# prototype-mark-II.net
KiCad netlist of a schematic drawn in EAGLE
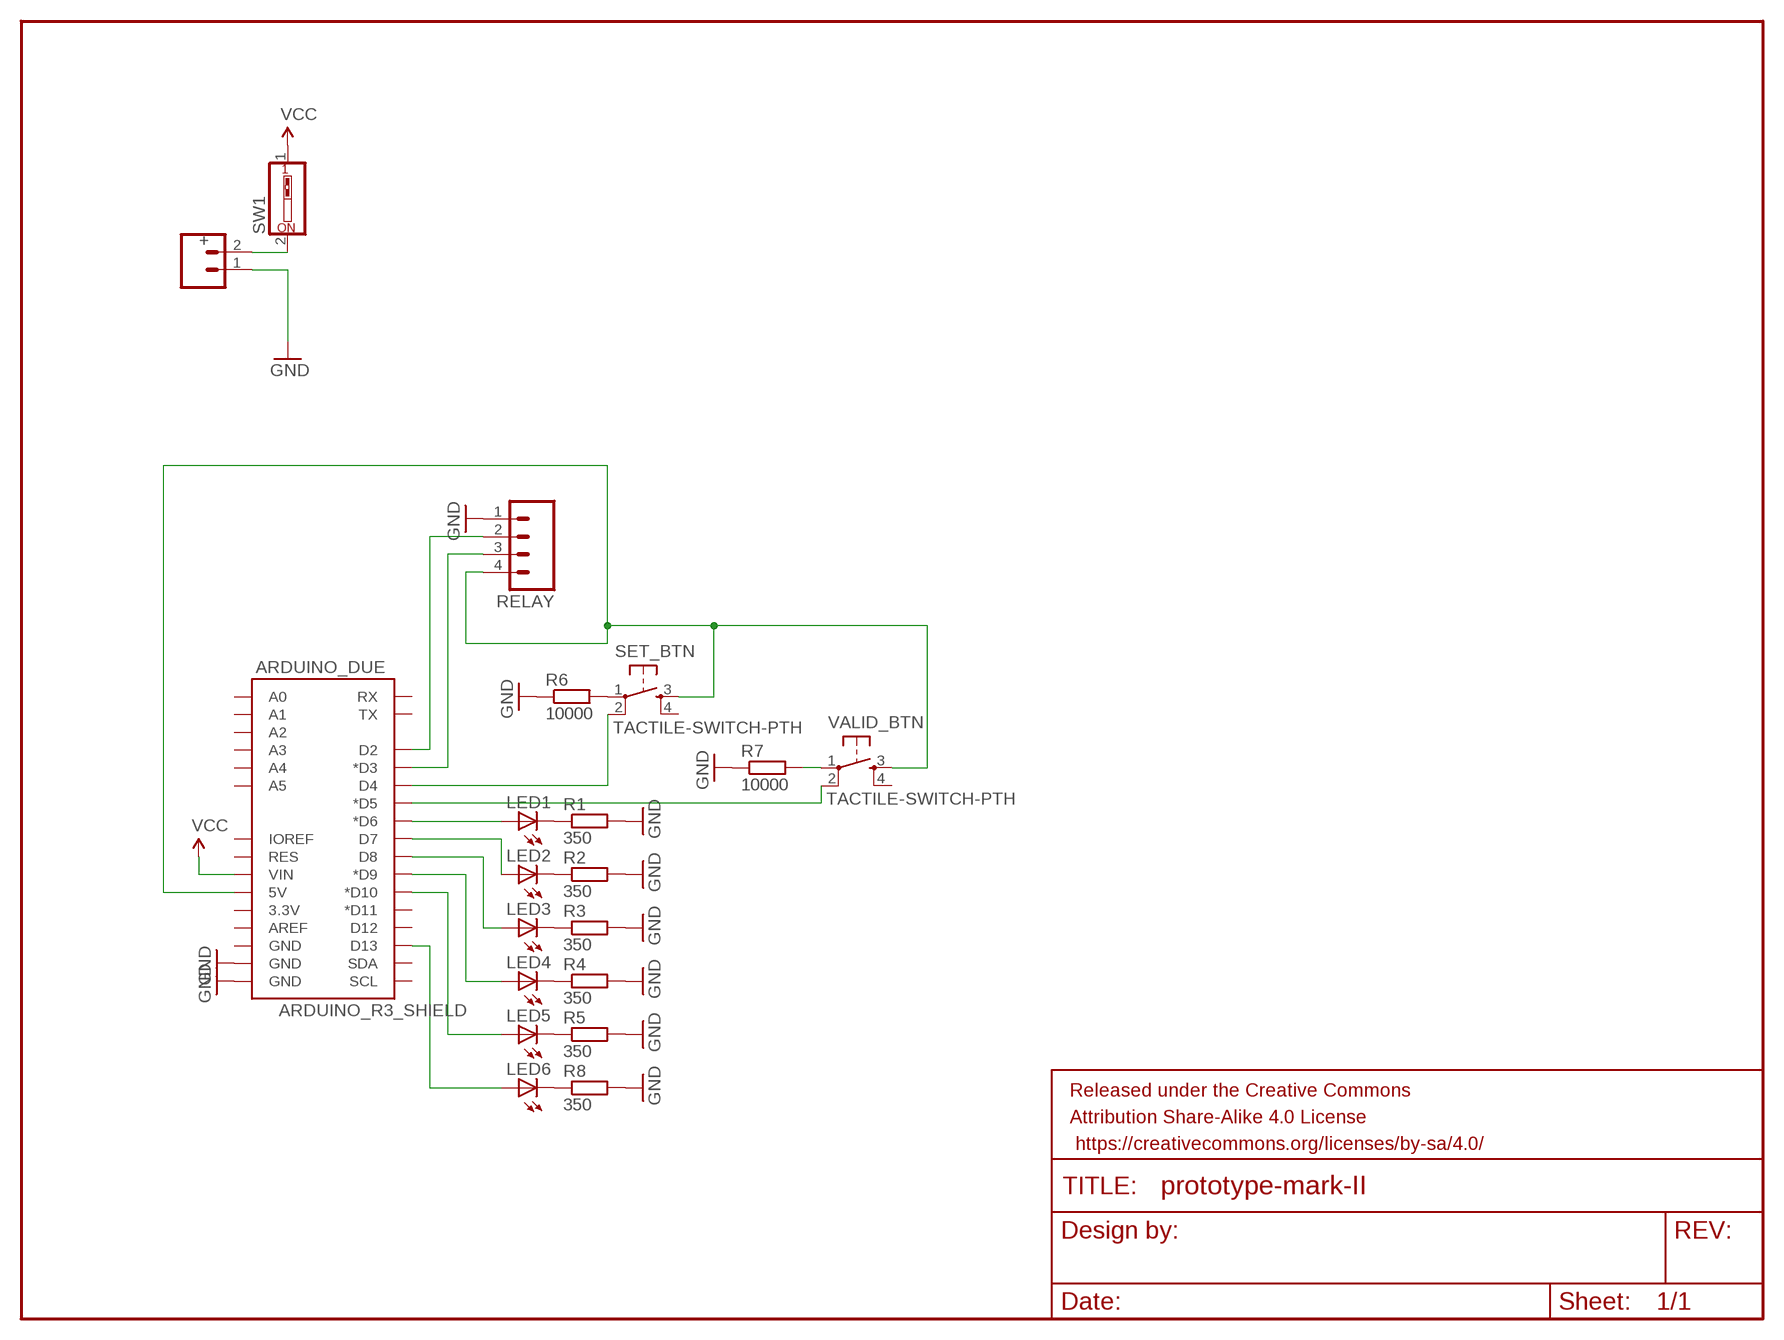
[diagram p0: schematic, sheet 1]

(export (version "E")
  (design (tool "Eeschema 10.0.6"))
  (components
    (comp (ref "+")
      (value "M02PTH")
      (footprint "eagle-import:1X02")
      (libsource (lib "eagle-import") (part "M02PTH"))
    )
    (comp (ref "ARDUINO_DUE")
      (value "ARDUINO_R3_SHIELD")
      (footprint "eagle-import:UNO_R3_SHIELD")
      (libsource (lib "eagle-import") (part "ARDUINO_R3_SHIELD"))
    )
    (comp (ref "FRAME1")
      (value "FRAME-LETTERNO_PACKAGE")
      (footprint "eagle-import:DUMMY")
      (fields (field (name "DESIGNER") "Nobody"))
      (libsource (lib "eagle-import") (part "FRAME-LETTERNO_PACKAGE"))
    )
    (comp (ref "LED1")
      (value "LED3MM")
      (footprint "eagle-import:LED3MM")
      (libsource (lib "eagle-import") (part "LED3MM"))
    )
    (comp (ref "LED2")
      (value "LED3MM")
      (footprint "eagle-import:LED3MM")
      (libsource (lib "eagle-import") (part "LED3MM"))
    )
    (comp (ref "LED3")
      (value "LED3MM")
      (footprint "eagle-import:LED3MM")
      (libsource (lib "eagle-import") (part "LED3MM"))
    )
    (comp (ref "LED4")
      (value "LED3MM")
      (footprint "eagle-import:LED3MM")
      (libsource (lib "eagle-import") (part "LED3MM"))
    )
    (comp (ref "LED5")
      (value "LED3MM")
      (footprint "eagle-import:LED3MM")
      (libsource (lib "eagle-import") (part "LED3MM"))
    )
    (comp (ref "LED6")
      (value "LED3MM")
      (footprint "eagle-import:LED3MM")
      (libsource (lib "eagle-import") (part "LED3MM"))
    )
    (comp (ref "R1")
      (value "350")
      (footprint "eagle-import:0204_7")
      (libsource (lib "eagle-import") (part "R0204/7"))
    )
    (comp (ref "R2")
      (value "350")
      (footprint "eagle-import:0204_7")
      (libsource (lib "eagle-import") (part "R0204/7"))
    )
    (comp (ref "R3")
      (value "350")
      (footprint "eagle-import:0204_7")
      (libsource (lib "eagle-import") (part "R0204/7"))
    )
    (comp (ref "R4")
      (value "350")
      (footprint "eagle-import:0204_7")
      (libsource (lib "eagle-import") (part "R0204/7"))
    )
    (comp (ref "R5")
      (value "350")
      (footprint "eagle-import:0204_7")
      (libsource (lib "eagle-import") (part "R0204/7"))
    )
    (comp (ref "R6")
      (value "10000")
      (footprint "eagle-import:0204_7")
      (libsource (lib "eagle-import") (part "R0204/7"))
    )
    (comp (ref "R7")
      (value "10000")
      (footprint "eagle-import:0204_7")
      (libsource (lib "eagle-import") (part "R0204/7"))
    )
    (comp (ref "R8")
      (value "350")
      (footprint "eagle-import:0204_7")
      (libsource (lib "eagle-import") (part "R0204/7"))
    )
    (comp (ref "RELAY")
      (value "M04PTH")
      (footprint "eagle-import:1X04")
      (libsource (lib "eagle-import") (part "M04PTH"))
    )
    (comp (ref "SET_BTN")
      (value "TACTILE-SWITCH-PTH")
      (footprint "eagle-import:TAC-SWITCH-PTH")
      (libsource (lib "eagle-import") (part "TACTILE-SWITCH-PTH"))
    )
    (comp (ref "SW1")
      (value "SW_DIP-1")
      (footprint "eagle-import:EDG-01")
      (libsource (lib "eagle-import") (part "SW_DIP-1"))
    )
    (comp (ref "VALID_BTN")
      (value "TACTILE-SWITCH-PTH")
      (footprint "eagle-import:TAC-SWITCH-PTH")
      (libsource (lib "eagle-import") (part "TACTILE-SWITCH-PTH"))
    )
  )
  (nets
    (net (code "1") (name "GND") (class "Default")
      (node (ref "+") (pin "1") (pinfunction "1_1") (pintype "passive"))
      (node (ref "ARDUINO_DUE") (pin "GND@0") (pinfunction "GND_GND@0") (pintype "bidirectional"))
      (node (ref "ARDUINO_DUE") (pin "GND@1") (pinfunction "GND_GND@1") (pintype "bidirectional"))
      (node (ref "R1") (pin "2") (pinfunction "2_2") (pintype "passive"))
      (node (ref "R2") (pin "2") (pinfunction "2_2") (pintype "passive"))
      (node (ref "R3") (pin "2") (pinfunction "2_2") (pintype "passive"))
      (node (ref "R4") (pin "2") (pinfunction "2_2") (pintype "passive"))
      (node (ref "R5") (pin "2") (pinfunction "2_2") (pintype "passive"))
      (node (ref "R6") (pin "1") (pinfunction "1_1") (pintype "passive"))
      (node (ref "R7") (pin "1") (pinfunction "1_1") (pintype "passive"))
      (node (ref "R8") (pin "2") (pinfunction "2_2") (pintype "passive"))
      (node (ref "RELAY") (pin "1") (pinfunction "1_1") (pintype "passive"))
    )
    (net (code "2") (name "Net-(+-Pad2)") (class "Default")
      (node (ref "+") (pin "2") (pinfunction "2_2") (pintype "passive"))
      (node (ref "SW1") (pin "2") (pinfunction "2_2") (pintype "passive"))
    )
    (net (code "3") (name "Net-(ARDUINO_DUE-*D3)") (class "Default")
      (node (ref "ARDUINO_DUE") (pin "D3") (pinfunction "*D3_D3") (pintype "bidirectional"))
      (node (ref "RELAY") (pin "3") (pinfunction "3_3") (pintype "passive"))
    )
    (net (code "4") (name "Net-(ARDUINO_DUE-*D5)") (class "Default")
      (node (ref "ARDUINO_DUE") (pin "D5") (pinfunction "*D5_D5") (pintype "bidirectional"))
      (node (ref "VALID_BTN") (pin "2") (pinfunction "2_2") (pintype "passive"))
    )
    (net (code "5") (name "Net-(ARDUINO_DUE-*D6)") (class "Default")
      (node (ref "ARDUINO_DUE") (pin "D6") (pinfunction "*D6_D6") (pintype "bidirectional"))
      (node (ref "LED1") (pin "A") (pinfunction "A_A") (pintype "passive"))
    )
    (net (code "6") (name "Net-(ARDUINO_DUE-*D9)") (class "Default")
      (node (ref "ARDUINO_DUE") (pin "D9") (pinfunction "*D9_D9") (pintype "bidirectional"))
      (node (ref "LED4") (pin "A") (pinfunction "A_A") (pintype "passive"))
    )
    (net (code "7") (name "Net-(ARDUINO_DUE-*D10)") (class "Default")
      (node (ref "ARDUINO_DUE") (pin "D10") (pinfunction "*D10_D10") (pintype "bidirectional"))
      (node (ref "LED5") (pin "A") (pinfunction "A_A") (pintype "passive"))
    )
    (net (code "8") (name "Net-(ARDUINO_DUE-Pad5V)") (class "Default")
      (node (ref "ARDUINO_DUE") (pin "5V") (pinfunction "5V_5V") (pintype "bidirectional"))
      (node (ref "RELAY") (pin "4") (pinfunction "4_4") (pintype "passive"))
      (node (ref "SET_BTN") (pin "3") (pinfunction "3_3") (pintype "passive"))
      (node (ref "VALID_BTN") (pin "3") (pinfunction "3_3") (pintype "passive"))
    )
    (net (code "9") (name "Net-(ARDUINO_DUE-PadD2)") (class "Default")
      (node (ref "ARDUINO_DUE") (pin "D2") (pinfunction "D2_D2") (pintype "bidirectional"))
      (node (ref "RELAY") (pin "2") (pinfunction "2_2") (pintype "passive"))
    )
    (net (code "10") (name "Net-(ARDUINO_DUE-PadD4)") (class "Default")
      (node (ref "ARDUINO_DUE") (pin "D4") (pinfunction "D4_D4") (pintype "bidirectional"))
      (node (ref "SET_BTN") (pin "2") (pinfunction "2_2") (pintype "passive"))
    )
    (net (code "11") (name "Net-(ARDUINO_DUE-PadD7)") (class "Default")
      (node (ref "ARDUINO_DUE") (pin "D7") (pinfunction "D7_D7") (pintype "bidirectional"))
      (node (ref "LED2") (pin "A") (pinfunction "A_A") (pintype "passive"))
    )
    (net (code "12") (name "Net-(ARDUINO_DUE-PadD8)") (class "Default")
      (node (ref "ARDUINO_DUE") (pin "D8") (pinfunction "D8_D8") (pintype "bidirectional"))
      (node (ref "LED3") (pin "A") (pinfunction "A_A") (pintype "passive"))
    )
    (net (code "13") (name "Net-(ARDUINO_DUE-PadD13)") (class "Default")
      (node (ref "ARDUINO_DUE") (pin "D13") (pinfunction "D13_D13") (pintype "bidirectional"))
      (node (ref "LED6") (pin "A") (pinfunction "A_A") (pintype "passive"))
    )
    (net (code "14") (name "Net-(LED1-C)") (class "Default")
      (node (ref "LED1") (pin "K") (pinfunction "C_K") (pintype "passive"))
      (node (ref "R1") (pin "1") (pinfunction "1_1") (pintype "passive"))
    )
    (net (code "15") (name "Net-(LED2-C)") (class "Default")
      (node (ref "LED2") (pin "K") (pinfunction "C_K") (pintype "passive"))
      (node (ref "R2") (pin "1") (pinfunction "1_1") (pintype "passive"))
    )
    (net (code "16") (name "Net-(LED3-C)") (class "Default")
      (node (ref "LED3") (pin "K") (pinfunction "C_K") (pintype "passive"))
      (node (ref "R3") (pin "1") (pinfunction "1_1") (pintype "passive"))
    )
    (net (code "17") (name "Net-(LED4-C)") (class "Default")
      (node (ref "LED4") (pin "K") (pinfunction "C_K") (pintype "passive"))
      (node (ref "R4") (pin "1") (pinfunction "1_1") (pintype "passive"))
    )
    (net (code "18") (name "Net-(LED5-C)") (class "Default")
      (node (ref "LED5") (pin "K") (pinfunction "C_K") (pintype "passive"))
      (node (ref "R5") (pin "1") (pinfunction "1_1") (pintype "passive"))
    )
    (net (code "19") (name "Net-(LED6-C)") (class "Default")
      (node (ref "LED6") (pin "K") (pinfunction "C_K") (pintype "passive"))
      (node (ref "R8") (pin "1") (pinfunction "1_1") (pintype "passive"))
    )
    (net (code "20") (name "Net-(R6-Pad2)") (class "Default")
      (node (ref "R6") (pin "2") (pinfunction "2_2") (pintype "passive"))
      (node (ref "SET_BTN") (pin "1") (pinfunction "1_1") (pintype "passive"))
    )
    (net (code "21") (name "Net-(R7-Pad2)") (class "Default")
      (node (ref "R7") (pin "2") (pinfunction "2_2") (pintype "passive"))
      (node (ref "VALID_BTN") (pin "1") (pinfunction "1_1") (pintype "passive"))
    )
    (net (code "22") (name "VCC") (class "Default")
      (node (ref "ARDUINO_DUE") (pin "VIN") (pinfunction "VIN_VIN") (pintype "bidirectional"))
      (node (ref "SW1") (pin "1") (pinfunction "1_1") (pintype "passive"))
    )
    (net (code "23") (name "unconnected-(ARDUINO_DUE-*D11-PadD11)") (class "Default")
      (node (ref "ARDUINO_DUE") (pin "D11") (pinfunction "*D11_D11") (pintype "bidirectional"))
    )
    (net (code "24") (name "unconnected-(ARDUINO_DUE-GND-PadGND@2)") (class "Default")
      (node (ref "ARDUINO_DUE") (pin "GND@2") (pinfunction "GND_GND@2") (pintype "bidirectional"))
    )
    (net (code "25") (name "unconnected-(ARDUINO_DUE-Pad3.3V)") (class "Default")
      (node (ref "ARDUINO_DUE") (pin "3.3V") (pinfunction "3.3V_3.3V") (pintype "bidirectional"))
    )
    (net (code "26") (name "unconnected-(ARDUINO_DUE-PadA0)") (class "Default")
      (node (ref "ARDUINO_DUE") (pin "A0") (pinfunction "A0_A0") (pintype "bidirectional"))
    )
    (net (code "27") (name "unconnected-(ARDUINO_DUE-PadA1)") (class "Default")
      (node (ref "ARDUINO_DUE") (pin "A1") (pinfunction "A1_A1") (pintype "bidirectional"))
    )
    (net (code "28") (name "unconnected-(ARDUINO_DUE-PadA2)") (class "Default")
      (node (ref "ARDUINO_DUE") (pin "A2") (pinfunction "A2_A2") (pintype "bidirectional"))
    )
    (net (code "29") (name "unconnected-(ARDUINO_DUE-PadA3)") (class "Default")
      (node (ref "ARDUINO_DUE") (pin "A3") (pinfunction "A3_A3") (pintype "bidirectional"))
    )
    (net (code "30") (name "unconnected-(ARDUINO_DUE-PadA4)") (class "Default")
      (node (ref "ARDUINO_DUE") (pin "A4") (pinfunction "A4_A4") (pintype "bidirectional"))
    )
    (net (code "31") (name "unconnected-(ARDUINO_DUE-PadA5)") (class "Default")
      (node (ref "ARDUINO_DUE") (pin "A5") (pinfunction "A5_A5") (pintype "bidirectional"))
    )
    (net (code "32") (name "unconnected-(ARDUINO_DUE-PadAREF)") (class "Default")
      (node (ref "ARDUINO_DUE") (pin "AREF") (pinfunction "AREF_AREF") (pintype "bidirectional"))
    )
    (net (code "33") (name "unconnected-(ARDUINO_DUE-PadD12)") (class "Default")
      (node (ref "ARDUINO_DUE") (pin "D12") (pinfunction "D12_D12") (pintype "bidirectional"))
    )
    (net (code "34") (name "unconnected-(ARDUINO_DUE-PadIOREF)") (class "Default")
      (node (ref "ARDUINO_DUE") (pin "IOREF") (pinfunction "IOREF_IOREF") (pintype "bidirectional"))
    )
    (net (code "35") (name "unconnected-(ARDUINO_DUE-PadRES)") (class "Default")
      (node (ref "ARDUINO_DUE") (pin "RES") (pinfunction "RES_RES") (pintype "bidirectional"))
    )
    (net (code "36") (name "unconnected-(ARDUINO_DUE-PadRX)") (class "Default")
      (node (ref "ARDUINO_DUE") (pin "RX") (pinfunction "RX_RX") (pintype "bidirectional"))
    )
    (net (code "37") (name "unconnected-(ARDUINO_DUE-PadSCL)") (class "Default")
      (node (ref "ARDUINO_DUE") (pin "SCL") (pinfunction "SCL_SCL") (pintype "bidirectional"))
    )
    (net (code "38") (name "unconnected-(ARDUINO_DUE-PadSDA)") (class "Default")
      (node (ref "ARDUINO_DUE") (pin "SDA") (pinfunction "SDA_SDA") (pintype "bidirectional"))
    )
    (net (code "39") (name "unconnected-(ARDUINO_DUE-PadTX)") (class "Default")
      (node (ref "ARDUINO_DUE") (pin "TX") (pinfunction "TX_TX") (pintype "bidirectional"))
    )
    (net (code "40") (name "unconnected-(SET_BTN-Pad4)") (class "Default")
      (node (ref "SET_BTN") (pin "4") (pinfunction "4_4") (pintype "passive"))
    )
    (net (code "41") (name "unconnected-(VALID_BTN-Pad4)") (class "Default")
      (node (ref "VALID_BTN") (pin "4") (pinfunction "4_4") (pintype "passive"))
    )
  )
)
